# Keyboard.net
KiCad netlist of a schematic drawn in Altium Designer
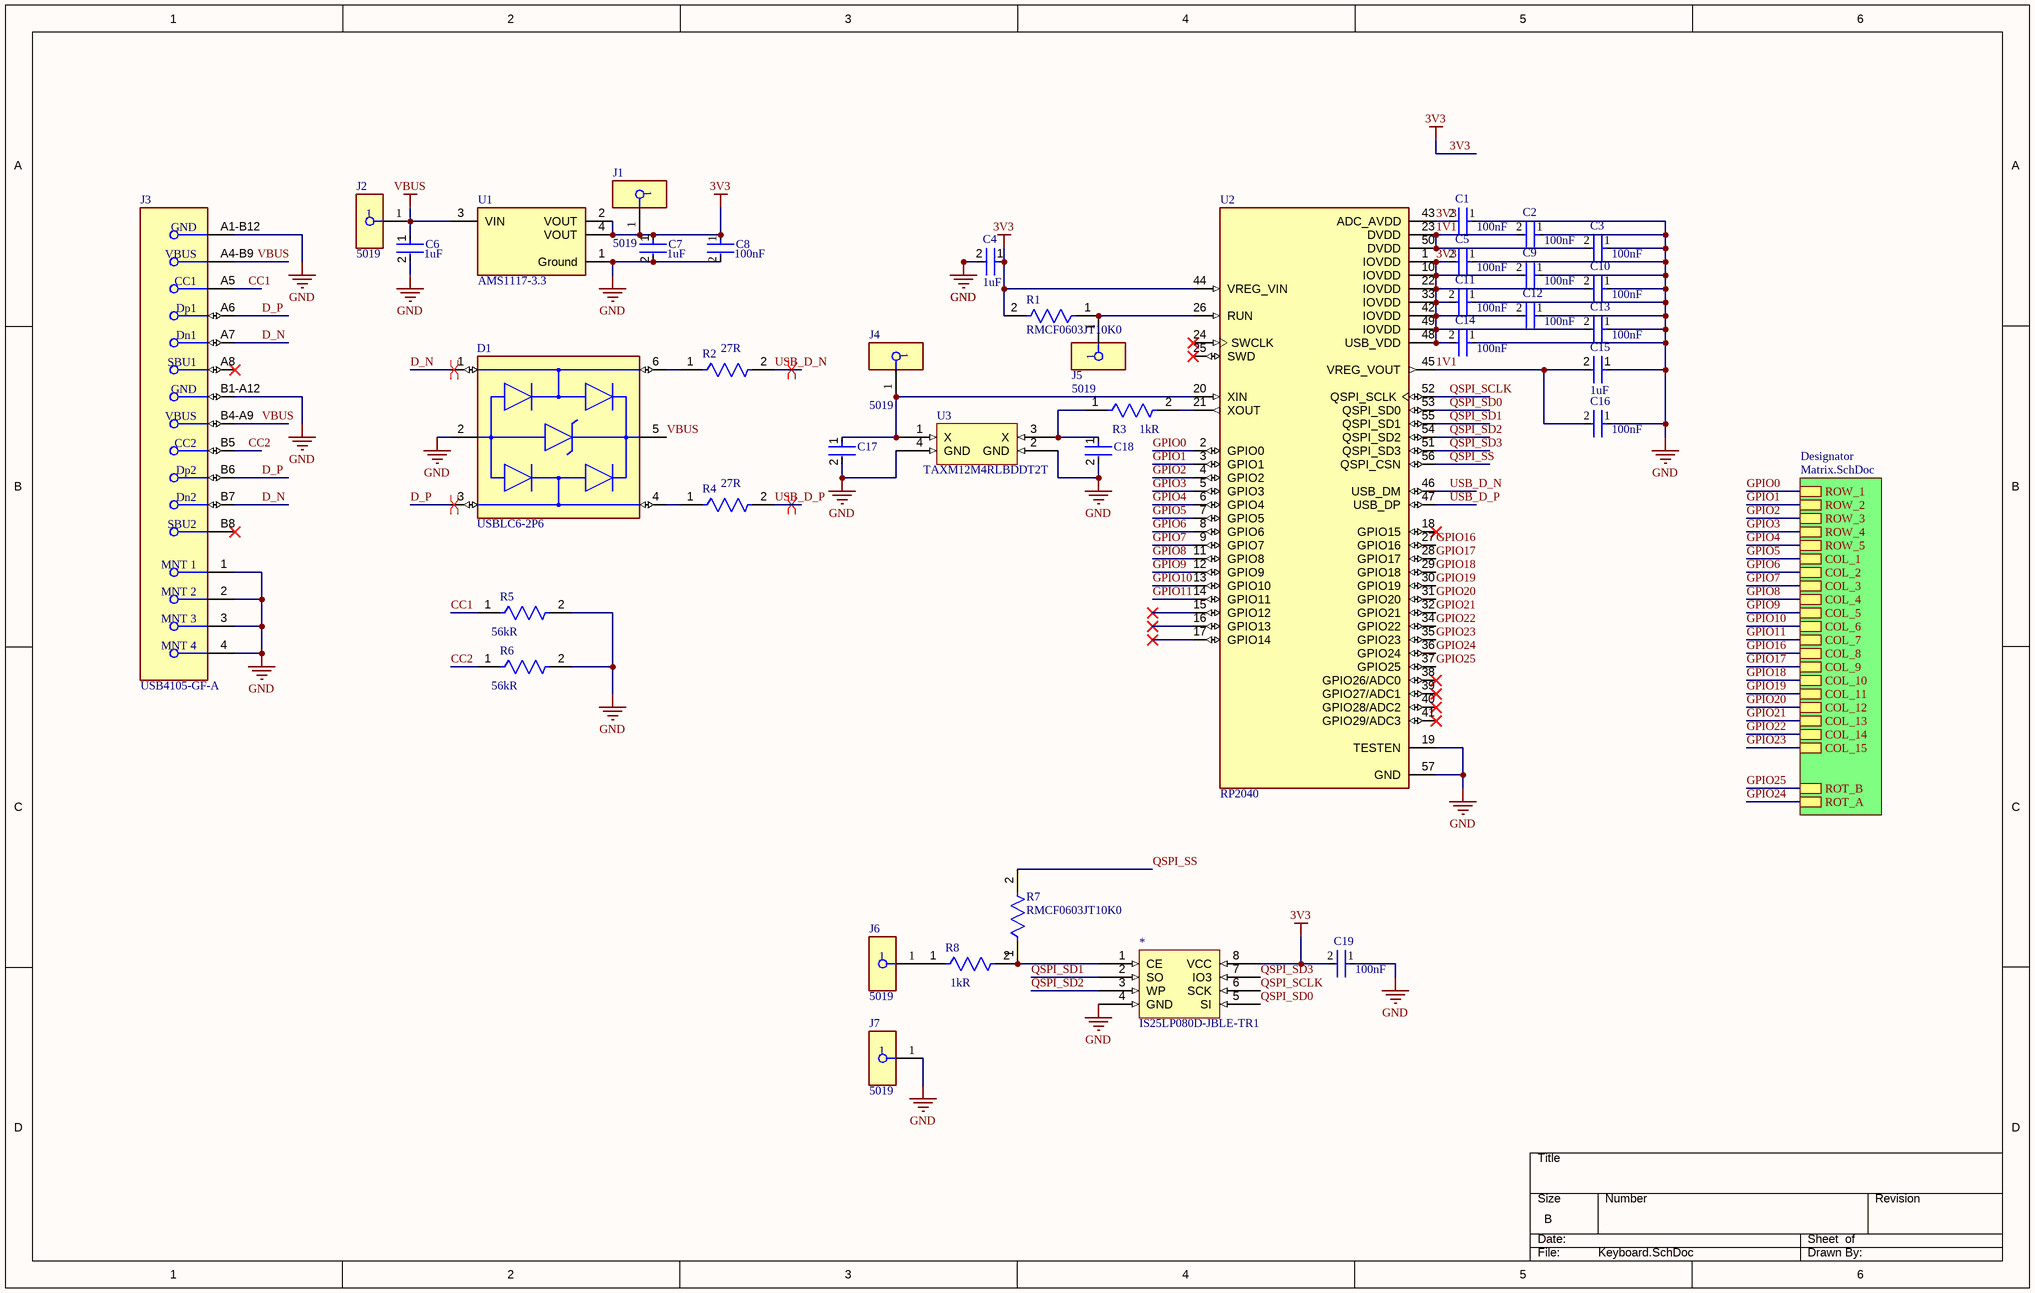
[diagram p0: Keyboard.SchDoc]

(export (version "E")
  (design (tool "Eeschema 10.0.6"))
  (components
    (comp (ref "*")
      (value "IS25LP080D-JBLE-TR1")
      (footprint "SOIC127P790X216-8N")
      (description "Flash")
      (libsource (lib "Brian Tan") (part "New symbol 1"))
    )
    (comp (ref "C1")
      (value "GRM155R71C104KA88J")
      (footprint "FP-GRM155-0_05-MFG")
      (fields
        (field (name "VOLTAGE") "16V")
        (field (name "TOLERANCE") "10%")
        (field (name "CAPACITANCE") "100nF")
      )
      (libsource (lib "Altium Content Vault") (part "b4654b650e69147ec39a6b967a45e02"))
    )
    (comp (ref "C2")
      (value "GRM155R71C104KA88J")
      (footprint "FP-GRM155-0_05-MFG")
      (fields
        (field (name "VOLTAGE") "16V")
        (field (name "TOLERANCE") "10%")
        (field (name "CAPACITANCE") "100nF")
      )
      (libsource (lib "Altium Content Vault") (part "b4654b650e69147ec39a6b967a45e02"))
    )
    (comp (ref "C3")
      (value "GRM155R71C104KA88J")
      (footprint "FP-GRM155-0_05-MFG")
      (fields
        (field (name "VOLTAGE") "16V")
        (field (name "TOLERANCE") "10%")
        (field (name "CAPACITANCE") "100nF")
      )
      (libsource (lib "Altium Content Vault") (part "b4654b650e69147ec39a6b967a45e02"))
    )
    (comp (ref "C4")
      (value "CL10A105KO8NNNC")
      (footprint "FP-CL10-IPC_A")
      (description "Cap Ceramic 1uF 16V X5R ±10% Pad SMD 0603 +85°C T/R")
      (fields
        (field (name "CAPACITANCE") "1uF")
        (field (name "TOLERANCE") "10%")
        (field (name "VOLTAGE") "16V")
      )
      (libsource (lib "Altium Content Vault") (part "b4654b650e69147ec39a6b967a45e02"))
    )
    (comp (ref "C5")
      (value "GRM155R71C104KA88J")
      (footprint "FP-GRM155-0_05-MFG")
      (fields
        (field (name "VOLTAGE") "16V")
        (field (name "TOLERANCE") "10%")
        (field (name "CAPACITANCE") "100nF")
      )
      (libsource (lib "Altium Content Vault") (part "b4654b650e69147ec39a6b967a45e02"))
    )
    (comp (ref "C6")
      (value "CL10A105KO8NNNC")
      (footprint "FP-CL10-IPC_A")
      (description "Cap Ceramic 1uF 16V X5R ±10% Pad SMD 0603 +85°C T/R")
      (fields
        (field (name "CAPACITANCE") "1uF")
        (field (name "TOLERANCE") "10%")
        (field (name "VOLTAGE") "16V")
      )
      (libsource (lib "Altium Content Vault") (part "b4654b650e69147ec39a6b967a45e02"))
    )
    (comp (ref "C7")
      (value "CL10A105KO8NNNC")
      (footprint "FP-CL10-IPC_A")
      (description "Cap Ceramic 1uF 16V X5R ±10% Pad SMD 0603 +85°C T/R")
      (fields
        (field (name "CAPACITANCE") "1uF")
        (field (name "TOLERANCE") "10%")
        (field (name "VOLTAGE") "16V")
      )
      (libsource (lib "Altium Content Vault") (part "b4654b650e69147ec39a6b967a45e02"))
    )
    (comp (ref "C8")
      (value "GRM155R71C104KA88J")
      (footprint "FP-GRM155-0_05-MFG")
      (fields
        (field (name "VOLTAGE") "16V")
        (field (name "TOLERANCE") "10%")
        (field (name "CAPACITANCE") "100nF")
      )
      (libsource (lib "Altium Content Vault") (part "b4654b650e69147ec39a6b967a45e02"))
    )
    (comp (ref "C9")
      (value "GRM155R71C104KA88J")
      (footprint "FP-GRM155-0_05-MFG")
      (fields
        (field (name "VOLTAGE") "16V")
        (field (name "TOLERANCE") "10%")
        (field (name "CAPACITANCE") "100nF")
      )
      (libsource (lib "Altium Content Vault") (part "b4654b650e69147ec39a6b967a45e02"))
    )
    (comp (ref "C10")
      (value "GRM155R71C104KA88J")
      (footprint "FP-GRM155-0_05-MFG")
      (fields
        (field (name "VOLTAGE") "16V")
        (field (name "TOLERANCE") "10%")
        (field (name "CAPACITANCE") "100nF")
      )
      (libsource (lib "Altium Content Vault") (part "b4654b650e69147ec39a6b967a45e02"))
    )
    (comp (ref "C11")
      (value "GRM155R71C104KA88J")
      (footprint "FP-GRM155-0_05-MFG")
      (fields
        (field (name "VOLTAGE") "16V")
        (field (name "TOLERANCE") "10%")
        (field (name "CAPACITANCE") "100nF")
      )
      (libsource (lib "Altium Content Vault") (part "b4654b650e69147ec39a6b967a45e02"))
    )
    (comp (ref "C12")
      (value "GRM155R71C104KA88J")
      (footprint "FP-GRM155-0_05-MFG")
      (fields
        (field (name "VOLTAGE") "16V")
        (field (name "TOLERANCE") "10%")
        (field (name "CAPACITANCE") "100nF")
      )
      (libsource (lib "Altium Content Vault") (part "b4654b650e69147ec39a6b967a45e02"))
    )
    (comp (ref "C13")
      (value "GRM155R71C104KA88J")
      (footprint "FP-GRM155-0_05-MFG")
      (fields
        (field (name "VOLTAGE") "16V")
        (field (name "TOLERANCE") "10%")
        (field (name "CAPACITANCE") "100nF")
      )
      (libsource (lib "Altium Content Vault") (part "b4654b650e69147ec39a6b967a45e02"))
    )
    (comp (ref "C14")
      (value "GRM155R71C104KA88J")
      (footprint "FP-GRM155-0_05-MFG")
      (fields
        (field (name "VOLTAGE") "16V")
        (field (name "TOLERANCE") "10%")
        (field (name "CAPACITANCE") "100nF")
      )
      (libsource (lib "Altium Content Vault") (part "b4654b650e69147ec39a6b967a45e02"))
    )
    (comp (ref "C15")
      (value "CL10A105KO8NNNC")
      (footprint "FP-CL10-IPC_A")
      (description "Cap Ceramic 1uF 16V X5R ±10% Pad SMD 0603 +85°C T/R")
      (fields
        (field (name "CAPACITANCE") "1uF")
        (field (name "TOLERANCE") "10%")
        (field (name "VOLTAGE") "16V")
      )
      (libsource (lib "Altium Content Vault") (part "b4654b650e69147ec39a6b967a45e02"))
    )
    (comp (ref "C16")
      (value "GRM155R71C104KA88J")
      (footprint "FP-GRM155-0_05-MFG")
      (fields
        (field (name "VOLTAGE") "16V")
        (field (name "TOLERANCE") "10%")
        (field (name "CAPACITANCE") "100nF")
      )
      (libsource (lib "Altium Content Vault") (part "b4654b650e69147ec39a6b967a45e02"))
    )
    (comp (ref "C17")
      (value "GQM2195C2E320JB12D")
      (footprint "FP-GQM219-0_15-IPC_C")
      (description "Ceramic Capacitor 32pF ±5% 250VDC C0G 0805 Paper T/R")
      (libsource (lib "Altium Content Vault") (part "b4654b650e69147ec39a6b967a45e02"))
    )
    (comp (ref "C18")
      (value "GQM2195C2E320JB12D")
      (footprint "FP-GQM219-0_15-IPC_C")
      (description "Ceramic Capacitor 32pF ±5% 250VDC C0G 0805 Paper T/R")
      (libsource (lib "Altium Content Vault") (part "b4654b650e69147ec39a6b967a45e02"))
    )
    (comp (ref "C19")
      (value "GRM155R71C104KA88J")
      (footprint "FP-GRM155-0_05-MFG")
      (fields
        (field (name "VOLTAGE") "16V")
        (field (name "TOLERANCE") "10%")
        (field (name "CAPACITANCE") "100nF")
      )
      (libsource (lib "Altium Content Vault") (part "b4654b650e69147ec39a6b967a45e02"))
    )
    (comp (ref "D1")
      (value "USBLC6-2P6")
      (footprint "FP-SOT-666-MFG")
      (description "TVS DIODE 5.25V 17V SOT666")
      (libsource (lib "Altium Content Vault") (part "c871e55f7e3243d341edbd671b98d92"))
    )
    (comp (ref "J1")
      (value "5019")
      (footprint "FP-5019-MFG")
      (libsource (lib "Altium Content Vault") (part "98815daf2f2c152b0c43f5ab9800df6"))
    )
    (comp (ref "J2")
      (value "5019")
      (footprint "FP-5019-MFG")
      (libsource (lib "") (part "98815daf2f2c152b0c43f5ab9800df6_2"))
    )
    (comp (ref "J3")
      (value "USB4105-GF-A")
      (footprint "FP-USB4105-GF-A-MFG")
      (description "CONN RCPT USB2.0 TYPEC 5A")
      (fields
        (field (name "MANUFACTURER") "GCT")
        (field (name "OCTOPART") "https://octopart.com/usb4105-gf-a-gct-106627878")
      )
      (libsource (lib "Altium Content Vault") (part "e7c17a616881a82b79941196b4bec10"))
    )
    (comp (ref "J4")
      (value "5019")
      (footprint "FP-5019-MFG")
      (libsource (lib "Altium Content Vault") (part "98815daf2f2c152b0c43f5ab9800df6"))
    )
    (comp (ref "J5")
      (value "5019")
      (footprint "FP-5019-MFG")
      (libsource (lib "") (part "98815daf2f2c152b0c43f5ab9800df6_1"))
    )
    (comp (ref "J6")
      (value "5019")
      (footprint "FP-5019-MFG")
      (libsource (lib "") (part "98815daf2f2c152b0c43f5ab9800df6_2"))
    )
    (comp (ref "J7")
      (value "5019")
      (footprint "FP-5019-MFG")
      (libsource (lib "") (part "98815daf2f2c152b0c43f5ab9800df6_2"))
    )
    (comp (ref "R1")
      (value "RMCF0603JT10K0")
      (footprint "FP-RMCF0603-IPC_C")
      (description "10kΩ ±5% 0.1W 0603 Thick Film Chip Resistor AEC-Q200 compliant")
      (fields (field (name "TOLERANCE") "5%"))
      (libsource (lib "Altium Content Vault") (part "1029c3af85768c4190bb7ad29bc67b5"))
    )
    (comp (ref "R2")
      (value "RMCF0603FT27R0")
      (footprint "FP-RMCF0603-IPC_B")
      (description "27Ω ±1% 0.1W 0603 Thick Film Chip Resistor AEC-Q200 compliant")
      (fields (field (name "RESISTANCE") "27R") (field (name "TOLERANCE") "1%"))
      (libsource (lib "Altium Content Vault") (part "1029c3af85768c4190bb7ad29bc67b5"))
    )
    (comp (ref "R3")
      (value "RC0603FR-071KL")
      (footprint "FP-RC0603-0_55-IPC_C")
      (description "RES 1K OHM 1% 1/10W 0603")
      (fields (field (name "RESISTANCE") "1kR") (field (name "TOLERANCE") "1%"))
      (libsource (lib "Altium Content Vault") (part "1029c3af85768c4190bb7ad29bc67b5"))
    )
    (comp (ref "R4")
      (value "RMCF0603FT27R0")
      (footprint "FP-RMCF0603-IPC_B")
      (description "27Ω ±1% 0.1W 0603 Thick Film Chip Resistor AEC-Q200 compliant")
      (fields (field (name "RESISTANCE") "27R") (field (name "TOLERANCE") "1%"))
      (libsource (lib "Altium Content Vault") (part "1029c3af85768c4190bb7ad29bc67b5"))
    )
    (comp (ref "R5")
      (value "RMCF1206JT56K0")
      (footprint "FP-RMCF1206-MFG")
      (description "56kΩ ±5% 0.25W 1206 Thick Film Chip Resistor AEC-Q200 compliant")
      (fields (field (name "RESISTANCE") "56kR") (field (name "TOLERANCE") "5%"))
      (libsource (lib "Altium Content Vault") (part "1029c3af85768c4190bb7ad29bc67b5"))
    )
    (comp (ref "R6")
      (value "RMCF1206JT56K0")
      (footprint "FP-RMCF1206-MFG")
      (description "56kΩ ±5% 0.25W 1206 Thick Film Chip Resistor AEC-Q200 compliant")
      (fields (field (name "RESISTANCE") "56kR") (field (name "TOLERANCE") "5%"))
      (libsource (lib "Altium Content Vault") (part "1029c3af85768c4190bb7ad29bc67b5"))
    )
    (comp (ref "R7")
      (value "RMCF0603JT10K0")
      (footprint "FP-RMCF0603-IPC_C")
      (description "10kΩ ±5% 0.1W 0603 Thick Film Chip Resistor AEC-Q200 compliant")
      (fields (field (name "TOLERANCE") "5%"))
      (libsource (lib "Altium Content Vault") (part "1029c3af85768c4190bb7ad29bc67b5"))
    )
    (comp (ref "R8")
      (value "RC0603FR-071KL")
      (footprint "FP-RC0603-0_55-IPC_C")
      (description "RES 1K OHM 1% 1/10W 0603")
      (fields (field (name "RESISTANCE") "1kR") (field (name "TOLERANCE") "1%"))
      (libsource (lib "Altium Content Vault") (part "1029c3af85768c4190bb7ad29bc67b5"))
    )
    (comp (ref "U1")
      (value "AMS1117-3.3")
      (footprint "FP-AMS1117-IPC_C")
      (description "LDO Voltage Regulators 1A, 3.3V")
      (fields
        (field (name "OCTOPART") "https://octopart.com/ams1117-3.3-advanced+monolithic+systems-25899300")
        (field (name "MANUFACTURER") "Advanced Monolithic Systems")
      )
      (libsource (lib "Altium Content Vault") (part "8bdbb5f8e77002000e30dd2845d0354"))
    )
    (comp (ref "U2")
      (value "RP2040")
      (footprint "QFN40P700X700X90-57N")
      (description "RP2040 chip for Raspberry Pi Pico - ARM® Cortex®-M0+ MCU 32-Bit")
      (fields (field (name "MF") "Raspberry Pi"))
      (libsource (lib "Brian Tan") (part "RP2040"))
    )
    (comp (ref "U3")
      (value "TAXM12M4RLBDDT2T")
      (footprint "TAXM12M4RLBDDT2T")
      (description "Crystal 12MHz")
      (libsource (lib "Brian Tan") (part "TAXM12M4RLBDDT2T"))
    )
  )
  (nets
    (net (code "1") (name "/1V1") (class "Default")
      (node (ref "C15") (pin "2") (pinfunction "2_2") (pintype "passive"))
      (node (ref "C16") (pin "2") (pinfunction "2_2") (pintype "passive"))
      (node (ref "C2") (pin "2") (pinfunction "2_2") (pintype "passive"))
      (node (ref "C3") (pin "2") (pinfunction "2_2") (pintype "passive"))
      (node (ref "U2") (pin "23") (pinfunction "DVDD_23") (pintype "power_in"))
      (node (ref "U2") (pin "45") (pinfunction "VREG_VOUT_45") (pintype "output"))
      (node (ref "U2") (pin "50") (pinfunction "DVDD_50") (pintype "power_in"))
    )
    (net (code "2") (name "/CC1") (class "Default")
      (node (ref "J3") (pin "A5") (pinfunction "CC1_A5") (pintype "power_in"))
      (node (ref "R5") (pin "1") (pinfunction "1_1") (pintype "passive"))
    )
    (net (code "3") (name "/CC2") (class "Default")
      (node (ref "J3") (pin "B5") (pinfunction "CC2_B5") (pintype "bidirectional"))
      (node (ref "R6") (pin "1") (pinfunction "1_1") (pintype "passive"))
    )
    (net (code "4") (name "/D_N") (class "Default")
      (node (ref "D1") (pin "1") (pinfunction "I/O1_1") (pintype "bidirectional"))
      (node (ref "J3") (pin "A7") (pinfunction "Dn1_A7") (pintype "bidirectional"))
      (node (ref "J3") (pin "B7") (pinfunction "Dn2_B7") (pintype "bidirectional"))
    )
    (net (code "5") (name "/D_P") (class "Default")
      (node (ref "D1") (pin "3") (pinfunction "I/O2_3") (pintype "bidirectional"))
      (node (ref "J3") (pin "A6") (pinfunction "Dp1_A6") (pintype "bidirectional"))
      (node (ref "J3") (pin "B6") (pinfunction "Dp2_B6") (pintype "bidirectional"))
    )
    (net (code "6") (name "/GPIO0") (class "Default")
      (node (ref "U2") (pin "2") (pinfunction "GPIO0_2") (pintype "bidirectional"))
    )
    (net (code "7") (name "/GPIO1") (class "Default")
      (node (ref "U2") (pin "3") (pinfunction "GPIO1_3") (pintype "bidirectional"))
    )
    (net (code "8") (name "/GPIO2") (class "Default")
      (node (ref "U2") (pin "4") (pinfunction "GPIO2_4") (pintype "bidirectional"))
    )
    (net (code "9") (name "/GPIO3") (class "Default")
      (node (ref "U2") (pin "5") (pinfunction "GPIO3_5") (pintype "bidirectional"))
    )
    (net (code "10") (name "/GPIO4") (class "Default")
      (node (ref "U2") (pin "6") (pinfunction "GPIO4_6") (pintype "bidirectional"))
    )
    (net (code "11") (name "/GPIO5") (class "Default")
      (node (ref "U2") (pin "7") (pinfunction "GPIO5_7") (pintype "bidirectional"))
    )
    (net (code "12") (name "/GPIO6") (class "Default")
      (node (ref "U2") (pin "8") (pinfunction "GPIO6_8") (pintype "bidirectional"))
    )
    (net (code "13") (name "/GPIO7") (class "Default")
      (node (ref "U2") (pin "9") (pinfunction "GPIO7_9") (pintype "bidirectional"))
    )
    (net (code "14") (name "/GPIO8") (class "Default")
      (node (ref "U2") (pin "11") (pinfunction "GPIO8_11") (pintype "bidirectional"))
    )
    (net (code "15") (name "/GPIO9") (class "Default")
      (node (ref "U2") (pin "12") (pinfunction "GPIO9_12") (pintype "bidirectional"))
    )
    (net (code "16") (name "/GPIO10") (class "Default")
      (node (ref "U2") (pin "13") (pinfunction "GPIO10_13") (pintype "bidirectional"))
    )
    (net (code "17") (name "/GPIO11") (class "Default")
      (node (ref "U2") (pin "14") (pinfunction "GPIO11_14") (pintype "bidirectional"))
    )
    (net (code "18") (name "/GPIO16") (class "Default")
      (node (ref "U2") (pin "27") (pinfunction "GPIO16_27") (pintype "bidirectional"))
    )
    (net (code "19") (name "/GPIO17") (class "Default")
      (node (ref "U2") (pin "28") (pinfunction "GPIO17_28") (pintype "bidirectional"))
    )
    (net (code "20") (name "/GPIO18") (class "Default")
      (node (ref "U2") (pin "29") (pinfunction "GPIO18_29") (pintype "bidirectional"))
    )
    (net (code "21") (name "/GPIO19") (class "Default")
      (node (ref "U2") (pin "30") (pinfunction "GPIO19_30") (pintype "bidirectional"))
    )
    (net (code "22") (name "/GPIO20") (class "Default")
      (node (ref "U2") (pin "31") (pinfunction "GPIO20_31") (pintype "bidirectional"))
    )
    (net (code "23") (name "/GPIO21") (class "Default")
      (node (ref "U2") (pin "32") (pinfunction "GPIO21_32") (pintype "bidirectional"))
    )
    (net (code "24") (name "/GPIO22") (class "Default")
      (node (ref "U2") (pin "34") (pinfunction "GPIO22_34") (pintype "bidirectional"))
    )
    (net (code "25") (name "/GPIO23") (class "Default")
      (node (ref "U2") (pin "35") (pinfunction "GPIO23_35") (pintype "bidirectional"))
    )
    (net (code "26") (name "/GPIO24") (class "Default")
      (node (ref "U2") (pin "36") (pinfunction "GPIO24_36") (pintype "bidirectional"))
    )
    (net (code "27") (name "/GPIO25") (class "Default")
      (node (ref "U2") (pin "37") (pinfunction "GPIO25_37") (pintype "bidirectional"))
    )
    (net (code "28") (name "/QSPI_SCLK") (class "Default")
      (node (ref "*") (pin "6") (pinfunction "SCK_6") (pintype "input"))
      (node (ref "U2") (pin "52") (pinfunction "QSPI_SCLK_52") (pintype "bidirectional"))
    )
    (net (code "29") (name "/QSPI_SD0") (class "Default")
      (node (ref "*") (pin "5") (pinfunction "SI_5") (pintype "input"))
      (node (ref "U2") (pin "53") (pinfunction "QSPI_SD0_53") (pintype "bidirectional"))
    )
    (net (code "30") (name "/QSPI_SD1") (class "Default")
      (node (ref "*") (pin "2") (pinfunction "SO_2") (pintype "input"))
      (node (ref "U2") (pin "55") (pinfunction "QSPI_SD1_55") (pintype "bidirectional"))
    )
    (net (code "31") (name "/QSPI_SD2") (class "Default")
      (node (ref "*") (pin "3") (pinfunction "WP_3") (pintype "input"))
      (node (ref "U2") (pin "54") (pinfunction "QSPI_SD2_54") (pintype "bidirectional"))
    )
    (net (code "32") (name "/QSPI_SD3") (class "Default")
      (node (ref "*") (pin "7") (pinfunction "IO3_7") (pintype "input"))
      (node (ref "U2") (pin "51") (pinfunction "QSPI_SD3_51") (pintype "bidirectional"))
    )
    (net (code "33") (name "/QSPI_SS") (class "Default")
      (node (ref "R7") (pin "2") (pinfunction "2_2") (pintype "passive"))
      (node (ref "U2") (pin "56") (pinfunction "QSPI_CSN_56") (pintype "bidirectional"))
    )
    (net (code "34") (name "/USB_D_N") (class "Default")
      (node (ref "R2") (pin "2") (pinfunction "2_2") (pintype "passive"))
      (node (ref "U2") (pin "46") (pinfunction "USB_DM_46") (pintype "bidirectional"))
    )
    (net (code "35") (name "/USB_D_P") (class "Default")
      (node (ref "R4") (pin "2") (pinfunction "2_2") (pintype "passive"))
      (node (ref "U2") (pin "47") (pinfunction "USB_DP_47") (pintype "bidirectional"))
    )
    (net (code "36") (name "3V3") (class "Default")
      (node (ref "*") (pin "8") (pinfunction "VCC_8") (pintype "input"))
      (node (ref "C1") (pin "2") (pinfunction "2_2") (pintype "passive"))
      (node (ref "C10") (pin "2") (pinfunction "2_2") (pintype "passive"))
      (node (ref "C11") (pin "2") (pinfunction "2_2") (pintype "passive"))
      (node (ref "C12") (pin "2") (pinfunction "2_2") (pintype "passive"))
      (node (ref "C13") (pin "2") (pinfunction "2_2") (pintype "passive"))
      (node (ref "C14") (pin "2") (pinfunction "2_2") (pintype "passive"))
      (node (ref "C19") (pin "2") (pinfunction "2_2") (pintype "passive"))
      (node (ref "C4") (pin "1") (pinfunction "1_1") (pintype "passive"))
      (node (ref "C5") (pin "2") (pinfunction "2_2") (pintype "passive"))
      (node (ref "C7") (pin "1") (pinfunction "1_1") (pintype "passive"))
      (node (ref "C8") (pin "1") (pinfunction "1_1") (pintype "passive"))
      (node (ref "C9") (pin "2") (pinfunction "2_2") (pintype "passive"))
      (node (ref "J1") (pin "1") (pinfunction "1_1") (pintype "passive"))
      (node (ref "R1") (pin "2") (pinfunction "2_2") (pintype "passive"))
      (node (ref "U1") (pin "2") (pinfunction "VOUT_2") (pintype "passive"))
      (node (ref "U1") (pin "4") (pinfunction "VOUT_4") (pintype "passive"))
      (node (ref "U2") (pin "1") (pinfunction "IOVDD_1") (pintype "power_in"))
      (node (ref "U2") (pin "10") (pinfunction "IOVDD_10") (pintype "power_in"))
      (node (ref "U2") (pin "22") (pinfunction "IOVDD_22") (pintype "power_in"))
      (node (ref "U2") (pin "33") (pinfunction "IOVDD_33") (pintype "power_in"))
      (node (ref "U2") (pin "42") (pinfunction "IOVDD_42") (pintype "power_in"))
      (node (ref "U2") (pin "43") (pinfunction "ADC_AVDD_43") (pintype "power_in"))
      (node (ref "U2") (pin "44") (pinfunction "VREG_VIN_44") (pintype "input"))
      (node (ref "U2") (pin "48") (pinfunction "USB_VDD_48") (pintype "power_in"))
      (node (ref "U2") (pin "49") (pinfunction "IOVDD_49") (pintype "power_in"))
    )
    (net (code "37") (name "GND") (class "Default")
      (node (ref "*") (pin "4") (pinfunction "GND_4") (pintype "input"))
      (node (ref "C1") (pin "1") (pinfunction "1_1") (pintype "passive"))
      (node (ref "C10") (pin "1") (pinfunction "1_1") (pintype "passive"))
      (node (ref "C11") (pin "1") (pinfunction "1_1") (pintype "passive"))
      (node (ref "C12") (pin "1") (pinfunction "1_1") (pintype "passive"))
      (node (ref "C13") (pin "1") (pinfunction "1_1") (pintype "passive"))
      (node (ref "C14") (pin "1") (pinfunction "1_1") (pintype "passive"))
      (node (ref "C15") (pin "1") (pinfunction "1_1") (pintype "passive"))
      (node (ref "C16") (pin "1") (pinfunction "1_1") (pintype "passive"))
      (node (ref "C17") (pin "2") (pinfunction "2_2") (pintype "passive"))
      (node (ref "C18") (pin "2") (pinfunction "2_2") (pintype "passive"))
      (node (ref "C19") (pin "1") (pinfunction "1_1") (pintype "passive"))
      (node (ref "C2") (pin "1") (pinfunction "1_1") (pintype "passive"))
      (node (ref "C3") (pin "1") (pinfunction "1_1") (pintype "passive"))
      (node (ref "C4") (pin "2") (pinfunction "2_2") (pintype "passive"))
      (node (ref "C5") (pin "1") (pinfunction "1_1") (pintype "passive"))
      (node (ref "C6") (pin "2") (pinfunction "2_2") (pintype "passive"))
      (node (ref "C7") (pin "2") (pinfunction "2_2") (pintype "passive"))
      (node (ref "C8") (pin "2") (pinfunction "2_2") (pintype "passive"))
      (node (ref "C9") (pin "1") (pinfunction "1_1") (pintype "passive"))
      (node (ref "D1") (pin "2") (pinfunction "GND_2") (pintype "power_in"))
      (node (ref "J3") (pin "1") (pinfunction "MNT_1_1") (pintype "power_in"))
      (node (ref "J3") (pin "2") (pinfunction "MNT_2_2") (pintype "power_in"))
      (node (ref "J3") (pin "3") (pinfunction "MNT_3_3") (pintype "power_in"))
      (node (ref "J3") (pin "4") (pinfunction "MNT_4_4") (pintype "power_in"))
      (node (ref "J3") (pin "A1-B12") (pinfunction "GND_A1-B12") (pintype "power_in"))
      (node (ref "J3") (pin "B1-A12") (pinfunction "GND_B1-A12") (pintype "bidirectional"))
      (node (ref "J7") (pin "1") (pinfunction "1_1") (pintype "passive"))
      (node (ref "R5") (pin "2") (pinfunction "2_2") (pintype "passive"))
      (node (ref "R6") (pin "2") (pinfunction "2_2") (pintype "passive"))
      (node (ref "U1") (pin "1") (pinfunction "Ground_1") (pintype "power_in"))
      (node (ref "U2") (pin "19") (pinfunction "TESTEN_19") (pintype "passive"))
      (node (ref "U2") (pin "57") (pinfunction "GND_57") (pintype "power_in"))
      (node (ref "U3") (pin "2") (pinfunction "GND_2") (pintype "input"))
      (node (ref "U3") (pin "4") (pinfunction "GND_4") (pintype "input"))
    )
    (net (code "38") (name "Net-(*-CE)") (class "Default")
      (node (ref "*") (pin "1") (pinfunction "CE_1") (pintype "input"))
      (node (ref "R7") (pin "1") (pinfunction "1_1") (pintype "passive"))
      (node (ref "R8") (pin "2") (pinfunction "2_2") (pintype "passive"))
    )
    (net (code "39") (name "Net-(C18-Pad1)") (class "Default")
      (node (ref "C18") (pin "1") (pinfunction "1_1") (pintype "passive"))
      (node (ref "R3") (pin "1") (pinfunction "1_1") (pintype "passive"))
      (node (ref "U3") (pin "3") (pinfunction "X_3") (pintype "input"))
    )
    (net (code "40") (name "Net-(D1-I{slash}O1-Pad6)") (class "Default")
      (node (ref "D1") (pin "6") (pinfunction "I/O1_6") (pintype "bidirectional"))
      (node (ref "R2") (pin "1") (pinfunction "1_1") (pintype "passive"))
    )
    (net (code "41") (name "Net-(D1-I{slash}O2-Pad4)") (class "Default")
      (node (ref "D1") (pin "4") (pinfunction "I/O2_4") (pintype "bidirectional"))
      (node (ref "R4") (pin "1") (pinfunction "1_1") (pintype "passive"))
    )
    (net (code "42") (name "Net-(J6-Pad1)") (class "Default")
      (node (ref "J6") (pin "1") (pinfunction "1_1") (pintype "passive"))
      (node (ref "R8") (pin "1") (pinfunction "1_1") (pintype "passive"))
    )
    (net (code "43") (name "Net-(U2-RUN)") (class "Default")
      (node (ref "J5") (pin "1") (pinfunction "1_1") (pintype "passive"))
      (node (ref "R1") (pin "1") (pinfunction "1_1") (pintype "passive"))
      (node (ref "U2") (pin "26") (pinfunction "RUN_26") (pintype "input"))
    )
    (net (code "44") (name "Net-(U2-XIN)") (class "Default")
      (node (ref "C17") (pin "1") (pinfunction "1_1") (pintype "passive"))
      (node (ref "J4") (pin "1") (pinfunction "1_1") (pintype "passive"))
      (node (ref "U2") (pin "20") (pinfunction "XIN_20") (pintype "input"))
      (node (ref "U3") (pin "1") (pinfunction "X_1") (pintype "input"))
    )
    (net (code "45") (name "Net-(U2-XOUT)") (class "Default")
      (node (ref "R3") (pin "2") (pinfunction "2_2") (pintype "passive"))
      (node (ref "U2") (pin "21") (pinfunction "XOUT_21") (pintype "output"))
    )
    (net (code "46") (name "VBUS") (class "Default")
      (node (ref "C6") (pin "1") (pinfunction "1_1") (pintype "passive"))
      (node (ref "D1") (pin "5") (pinfunction "VBUS_5") (pintype "power_in"))
      (node (ref "J2") (pin "1") (pinfunction "1_1") (pintype "passive"))
      (node (ref "J3") (pin "A4-B9") (pinfunction "VBUS_A4-B9") (pintype "power_in"))
      (node (ref "J3") (pin "B4-A9") (pinfunction "VBUS_B4-A9") (pintype "bidirectional"))
      (node (ref "U1") (pin "3") (pinfunction "VIN_3") (pintype "power_in"))
    )
    (net (code "47") (name "unconnected-(J3-SBU1-PadA8)") (class "Default")
      (node (ref "J3") (pin "A8") (pinfunction "SBU1_A8") (pintype "bidirectional+no_connect"))
    )
    (net (code "48") (name "unconnected-(J3-SBU2-PadB8)") (class "Default")
      (node (ref "J3") (pin "B8") (pinfunction "SBU2_B8") (pintype "power_in+no_connect"))
    )
    (net (code "49") (name "unconnected-(U2-GPIO12-Pad15)") (class "Default")
      (node (ref "U2") (pin "15") (pinfunction "GPIO12_15") (pintype "bidirectional+no_connect"))
    )
    (net (code "50") (name "unconnected-(U2-GPIO13-Pad16)") (class "Default")
      (node (ref "U2") (pin "16") (pinfunction "GPIO13_16") (pintype "bidirectional+no_connect"))
    )
    (net (code "51") (name "unconnected-(U2-GPIO14-Pad17)") (class "Default")
      (node (ref "U2") (pin "17") (pinfunction "GPIO14_17") (pintype "bidirectional+no_connect"))
    )
    (net (code "52") (name "unconnected-(U2-GPIO15-Pad18)") (class "Default")
      (node (ref "U2") (pin "18") (pinfunction "GPIO15_18") (pintype "bidirectional+no_connect"))
    )
    (net (code "53") (name "unconnected-(U2-GPIO26{slash}ADC0-Pad38)") (class "Default")
      (node (ref "U2") (pin "38") (pinfunction "GPIO26/ADC0_38") (pintype "bidirectional+no_connect"))
    )
    (net (code "54") (name "unconnected-(U2-GPIO27{slash}ADC1-Pad39)") (class "Default")
      (node (ref "U2") (pin "39") (pinfunction "GPIO27/ADC1_39") (pintype "bidirectional+no_connect"))
    )
    (net (code "55") (name "unconnected-(U2-GPIO28{slash}ADC2-Pad40)") (class "Default")
      (node (ref "U2") (pin "40") (pinfunction "GPIO28/ADC2_40") (pintype "bidirectional+no_connect"))
    )
    (net (code "56") (name "unconnected-(U2-GPIO29{slash}ADC3-Pad41)") (class "Default")
      (node (ref "U2") (pin "41") (pinfunction "GPIO29/ADC3_41") (pintype "bidirectional+no_connect"))
    )
    (net (code "57") (name "unconnected-(U2-SWCLK-Pad24)") (class "Default")
      (node (ref "U2") (pin "24") (pinfunction "SWCLK_24") (pintype "input+no_connect"))
    )
    (net (code "58") (name "unconnected-(U2-SWD-Pad25)") (class "Default")
      (node (ref "U2") (pin "25") (pinfunction "SWD_25") (pintype "bidirectional+no_connect"))
    )
  )
)
